# Externos_prueba.net
KiCad netlist of a schematic drawn in Altium Designer
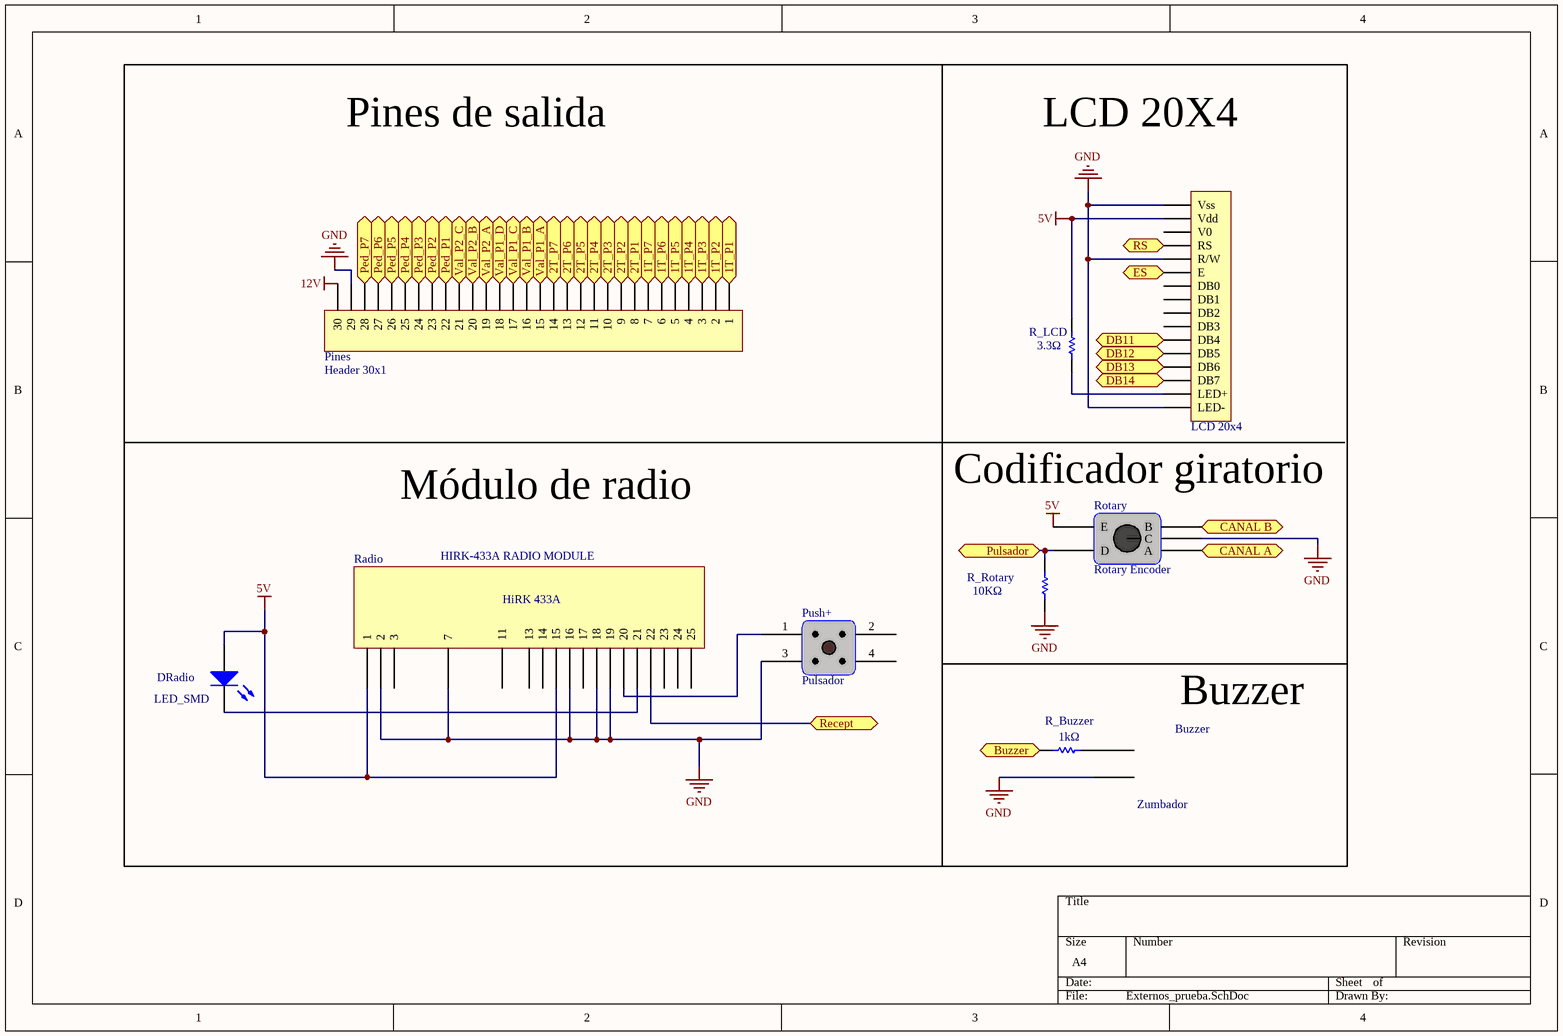
[diagram p0: Externos_prueba.SchDoc]

(export (version "E")
  (design (tool "Eeschema 10.0.6"))
  (components
    (comp (ref "DRadio")
      (value "LED_SMD")
      (footprint "LED_0805")
      (description "LED SMD")
      (fields (field (name "PUBLISHER") "Altium Limited"))
      (libsource (lib "Libreria_Organo") (part "LED_SMD"))
    )
    (comp (ref "LCD 20x4")
      (value "LCD 20x4")
      (footprint "LCD FORDATA (20x4)")
      (fields (field (name "PUBLISHER") "Altium Limited"))
      (libsource (lib "Libreria_Organo") (part "LCD 20x4"))
    )
    (comp (ref "Pines")
      (value "Header 30x1")
      (footprint "Header 1X30")
      (libsource (lib "Libreria_Organo") (part "Header 30x1"))
    )
    (comp (ref "Push+")
      (value "Pulsador")
      (footprint "Pulsador")
      (libsource (lib "Libreria_Organo") (part "Pulsador"))
    )
    (comp (ref "Radio")
      (value "HIRK-433A RADIO MODULE")
      (footprint "HIRK-433A Radio Module")
      (libsource (lib "Libreria_Organo") (part "HIRK-433A RADIO MODULE"))
    )
    (comp (ref "Rotary")
      (value "Rotary Encoder")
      (footprint "RotaryPCB")
      (libsource (lib "Libreria_Organo") (part "Rotary Encoder"))
    )
    (comp (ref "R_Buzzer")
      (value "1kΩ")
      (footprint "Resistencia_0805_N")
      (description "Res Chip 0805")
      (fields (field (name "PUBLISHER") "Altium Limited"))
      (libsource (lib "Libreria_Organo") (part "Resistencia"))
    )
    (comp (ref "R_LCD")
      (value "3.3Ω")
      (footprint "Resistencia_0805_N")
      (description "Res Chip 0805")
      (fields (field (name "PUBLISHER") "Altium Limited"))
      (libsource (lib "Libreria_Organo") (part "Resistencia"))
    )
    (comp (ref "R_Rotary")
      (value "10KΩ")
      (footprint "Resistencia_0805_N")
      (description "Res Chip 0805")
      (fields (field (name "PUBLISHER") "Altium Limited"))
      (libsource (lib "Libreria_Organo") (part "Resistencia"))
    )
    (comp (ref "Zumbador")
      (value "Buzzer")
      (footprint "Buzzer")
      (libsource (lib "Libreria_Organo") (part "Buzzer"))
    )
  )
  (nets
    (net (code "1") (name "/1T_P1") (class "Default")
      (node (ref "Pines") (pin "1") (pinfunction "1_1") (pintype "passive"))
    )
    (net (code "2") (name "/1T_P2") (class "Default")
      (node (ref "Pines") (pin "2") (pinfunction "2_2") (pintype "passive"))
    )
    (net (code "3") (name "/1T_P3") (class "Default")
      (node (ref "Pines") (pin "3") (pinfunction "3_3") (pintype "passive"))
    )
    (net (code "4") (name "/1T_P4") (class "Default")
      (node (ref "Pines") (pin "4") (pinfunction "4_4") (pintype "passive"))
    )
    (net (code "5") (name "/1T_P5") (class "Default")
      (node (ref "Pines") (pin "5") (pinfunction "5_5") (pintype "passive"))
    )
    (net (code "6") (name "/1T_P6") (class "Default")
      (node (ref "Pines") (pin "6") (pinfunction "6_6") (pintype "passive"))
    )
    (net (code "7") (name "/1T_P7") (class "Default")
      (node (ref "Pines") (pin "7") (pinfunction "7_7") (pintype "passive"))
    )
    (net (code "8") (name "/2T_P1") (class "Default")
      (node (ref "Pines") (pin "8") (pinfunction "8_8") (pintype "passive"))
    )
    (net (code "9") (name "/2T_P2") (class "Default")
      (node (ref "Pines") (pin "9") (pinfunction "9_9") (pintype "passive"))
    )
    (net (code "10") (name "/2T_P3") (class "Default")
      (node (ref "Pines") (pin "10") (pinfunction "10_10") (pintype "passive"))
    )
    (net (code "11") (name "/2T_P4") (class "Default")
      (node (ref "Pines") (pin "11") (pinfunction "11_11") (pintype "passive"))
    )
    (net (code "12") (name "/2T_P5") (class "Default")
      (node (ref "Pines") (pin "12") (pinfunction "12_12") (pintype "passive"))
    )
    (net (code "13") (name "/2T_P6") (class "Default")
      (node (ref "Pines") (pin "13") (pinfunction "13_13") (pintype "passive"))
    )
    (net (code "14") (name "/2T_P7") (class "Default")
      (node (ref "Pines") (pin "14") (pinfunction "14_14") (pintype "passive"))
    )
    (net (code "15") (name "/Buzzer") (class "Default")
      (node (ref "R_Buzzer") (pin "1") (pinfunction "1_1") (pintype "passive"))
    )
    (net (code "16") (name "/CANAL A") (class "Default")
      (node (ref "Rotary") (pin "A") (pinfunction "A_A") (pintype "passive"))
    )
    (net (code "17") (name "/CANAL B") (class "Default")
      (node (ref "Rotary") (pin "B") (pinfunction "B_B") (pintype "passive"))
    )
    (net (code "18") (name "/DB11") (class "Default")
      (node (ref "LCD 20x4") (pin "11") (pinfunction "DB4_11") (pintype "passive"))
    )
    (net (code "19") (name "/DB12") (class "Default")
      (node (ref "LCD 20x4") (pin "12") (pinfunction "DB5_12") (pintype "passive"))
    )
    (net (code "20") (name "/DB13") (class "Default")
      (node (ref "LCD 20x4") (pin "13") (pinfunction "DB6_13") (pintype "passive"))
    )
    (net (code "21") (name "/DB14") (class "Default")
      (node (ref "LCD 20x4") (pin "14") (pinfunction "DB7_14") (pintype "passive"))
    )
    (net (code "22") (name "/ES") (class "Default")
      (node (ref "LCD 20x4") (pin "6") (pinfunction "E_6") (pintype "passive"))
    )
    (net (code "23") (name "/Ped_P1") (class "Default")
      (node (ref "Pines") (pin "22") (pinfunction "22_22") (pintype "passive"))
    )
    (net (code "24") (name "/Ped_P2") (class "Default")
      (node (ref "Pines") (pin "23") (pinfunction "23_23") (pintype "passive"))
    )
    (net (code "25") (name "/Ped_P3") (class "Default")
      (node (ref "Pines") (pin "24") (pinfunction "24_24") (pintype "passive"))
    )
    (net (code "26") (name "/Ped_P4") (class "Default")
      (node (ref "Pines") (pin "25") (pinfunction "25_25") (pintype "passive"))
    )
    (net (code "27") (name "/Ped_P5") (class "Default")
      (node (ref "Pines") (pin "26") (pinfunction "26_26") (pintype "passive"))
    )
    (net (code "28") (name "/Ped_P6") (class "Default")
      (node (ref "Pines") (pin "27") (pinfunction "27_27") (pintype "passive"))
    )
    (net (code "29") (name "/Ped_P7") (class "Default")
      (node (ref "Pines") (pin "28") (pinfunction "28_28") (pintype "passive"))
    )
    (net (code "30") (name "/Pulsador") (class "Default")
      (node (ref "R_Rotary") (pin "2") (pinfunction "2_2") (pintype "passive"))
      (node (ref "Rotary") (pin "D") (pinfunction "D_D") (pintype "passive"))
    )
    (net (code "31") (name "/RS") (class "Default")
      (node (ref "LCD 20x4") (pin "4") (pinfunction "RS_4") (pintype "passive"))
    )
    (net (code "32") (name "/Recept") (class "Default")
      (node (ref "Radio") (pin "22") (pinfunction "22_22") (pintype "passive"))
    )
    (net (code "33") (name "/Val_P1_A") (class "Default")
      (node (ref "Pines") (pin "15") (pinfunction "15_15") (pintype "passive"))
    )
    (net (code "34") (name "/Val_P1_B") (class "Default")
      (node (ref "Pines") (pin "16") (pinfunction "16_16") (pintype "passive"))
    )
    (net (code "35") (name "/Val_P1_C") (class "Default")
      (node (ref "Pines") (pin "17") (pinfunction "17_17") (pintype "passive"))
    )
    (net (code "36") (name "/Val_P1_D") (class "Default")
      (node (ref "Pines") (pin "18") (pinfunction "18_18") (pintype "passive"))
    )
    (net (code "37") (name "/Val_P2_A") (class "Default")
      (node (ref "Pines") (pin "19") (pinfunction "19_19") (pintype "passive"))
    )
    (net (code "38") (name "/Val_P2_B") (class "Default")
      (node (ref "Pines") (pin "20") (pinfunction "20_20") (pintype "passive"))
    )
    (net (code "39") (name "/Val_P2_C") (class "Default")
      (node (ref "Pines") (pin "21") (pinfunction "21_21") (pintype "passive"))
    )
    (net (code "40") (name "5V") (class "Default")
      (node (ref "DRadio") (pin "1") (pinfunction "A_1") (pintype "passive"))
      (node (ref "LCD 20x4") (pin "2") (pinfunction "Vdd_2") (pintype "passive"))
      (node (ref "R_LCD") (pin "2") (pinfunction "2_2") (pintype "passive"))
      (node (ref "Radio") (pin "1") (pinfunction "1_1") (pintype "passive"))
      (node (ref "Radio") (pin "15") (pinfunction "15_15") (pintype "passive"))
      (node (ref "Rotary") (pin "E") (pinfunction "E_E") (pintype "passive"))
    )
    (net (code "41") (name "12V") (class "Default")
      (node (ref "Pines") (pin "30") (pinfunction "30_30") (pintype "passive"))
    )
    (net (code "42") (name "GND") (class "Default")
      (node (ref "LCD 20x4") (pin "1") (pinfunction "Vss_1") (pintype "passive"))
      (node (ref "LCD 20x4") (pin "16") (pinfunction "LED-_16") (pintype "passive"))
      (node (ref "LCD 20x4") (pin "5") (pinfunction "R/W_5") (pintype "passive"))
      (node (ref "Pines") (pin "29") (pinfunction "29_29") (pintype "passive"))
      (node (ref "Push+") (pin "3") (pinfunction "3_3") (pintype "passive"))
      (node (ref "R_Rotary") (pin "1") (pinfunction "1_1") (pintype "passive"))
      (node (ref "Radio") (pin "16") (pinfunction "16_16") (pintype "passive"))
      (node (ref "Radio") (pin "18") (pinfunction "18_18") (pintype "passive"))
      (node (ref "Radio") (pin "19") (pinfunction "19_19") (pintype "passive"))
      (node (ref "Radio") (pin "2") (pinfunction "2_2") (pintype "passive"))
      (node (ref "Radio") (pin "7") (pinfunction "7_7") (pintype "passive"))
      (node (ref "Rotary") (pin "C") (pinfunction "C_C") (pintype "passive"))
      (node (ref "Zumbador") (pin "2") (pinfunction "2_2") (pintype "passive"))
    )
    (net (code "43") (name "Net-(DRadio-K)") (class "Default")
      (node (ref "DRadio") (pin "2") (pinfunction "K_2") (pintype "passive"))
      (node (ref "Radio") (pin "21") (pinfunction "21_21") (pintype "passive"))
    )
    (net (code "44") (name "Net-(LCD 20x4-LED+)") (class "Default")
      (node (ref "LCD 20x4") (pin "15") (pinfunction "LED+_15") (pintype "passive"))
      (node (ref "R_LCD") (pin "1") (pinfunction "1_1") (pintype "passive"))
    )
    (net (code "45") (name "Net-(Push+-Pad1)") (class "Default")
      (node (ref "Push+") (pin "1") (pinfunction "1_1") (pintype "passive"))
      (node (ref "Radio") (pin "20") (pinfunction "20_20") (pintype "passive"))
    )
    (net (code "46") (name "Net-(R_Buzzer-Pad2)") (class "Default")
      (node (ref "R_Buzzer") (pin "2") (pinfunction "2_2") (pintype "passive"))
      (node (ref "Zumbador") (pin "1") (pinfunction "1_1") (pintype "passive"))
    )
    (net (code "47") (name "unconnected-(LCD 20x4-DB0-Pad7)") (class "Default")
      (node (ref "LCD 20x4") (pin "7") (pinfunction "DB0_7") (pintype "passive"))
    )
    (net (code "48") (name "unconnected-(LCD 20x4-DB1-Pad8)") (class "Default")
      (node (ref "LCD 20x4") (pin "8") (pinfunction "DB1_8") (pintype "passive"))
    )
    (net (code "49") (name "unconnected-(LCD 20x4-DB2-Pad9)") (class "Default")
      (node (ref "LCD 20x4") (pin "9") (pinfunction "DB2_9") (pintype "passive"))
    )
    (net (code "50") (name "unconnected-(LCD 20x4-DB3-Pad10)") (class "Default")
      (node (ref "LCD 20x4") (pin "10") (pinfunction "DB3_10") (pintype "passive"))
    )
    (net (code "51") (name "unconnected-(LCD 20x4-V0-Pad3)") (class "Default")
      (node (ref "LCD 20x4") (pin "3") (pinfunction "V0_3") (pintype "passive"))
    )
    (net (code "52") (name "unconnected-(Push+-Pad2)") (class "Default")
      (node (ref "Push+") (pin "2") (pinfunction "2_2") (pintype "passive"))
    )
    (net (code "53") (name "unconnected-(Push+-Pad4)") (class "Default")
      (node (ref "Push+") (pin "4") (pinfunction "4_4") (pintype "passive"))
    )
    (net (code "54") (name "unconnected-(Radio-Pad3)") (class "Default")
      (node (ref "Radio") (pin "3") (pinfunction "3_3") (pintype "passive"))
    )
    (net (code "55") (name "unconnected-(Radio-Pad11)") (class "Default")
      (node (ref "Radio") (pin "11") (pinfunction "11_11") (pintype "passive"))
    )
    (net (code "56") (name "unconnected-(Radio-Pad13)") (class "Default")
      (node (ref "Radio") (pin "13") (pinfunction "13_13") (pintype "passive"))
    )
    (net (code "57") (name "unconnected-(Radio-Pad14)") (class "Default")
      (node (ref "Radio") (pin "14") (pinfunction "14_14") (pintype "passive"))
    )
    (net (code "58") (name "unconnected-(Radio-Pad17)") (class "Default")
      (node (ref "Radio") (pin "17") (pinfunction "17_17") (pintype "passive"))
    )
    (net (code "59") (name "unconnected-(Radio-Pad23)") (class "Default")
      (node (ref "Radio") (pin "23") (pinfunction "23_23") (pintype "passive"))
    )
    (net (code "60") (name "unconnected-(Radio-Pad24)") (class "Default")
      (node (ref "Radio") (pin "24") (pinfunction "24_24") (pintype "passive"))
    )
    (net (code "61") (name "unconnected-(Radio-Pad25)") (class "Default")
      (node (ref "Radio") (pin "25") (pinfunction "25_25") (pintype "passive"))
    )
  )
)
